# Instigator2012ControllerBoard.net
KiCad netlist of a schematic drawn in Altium Designer
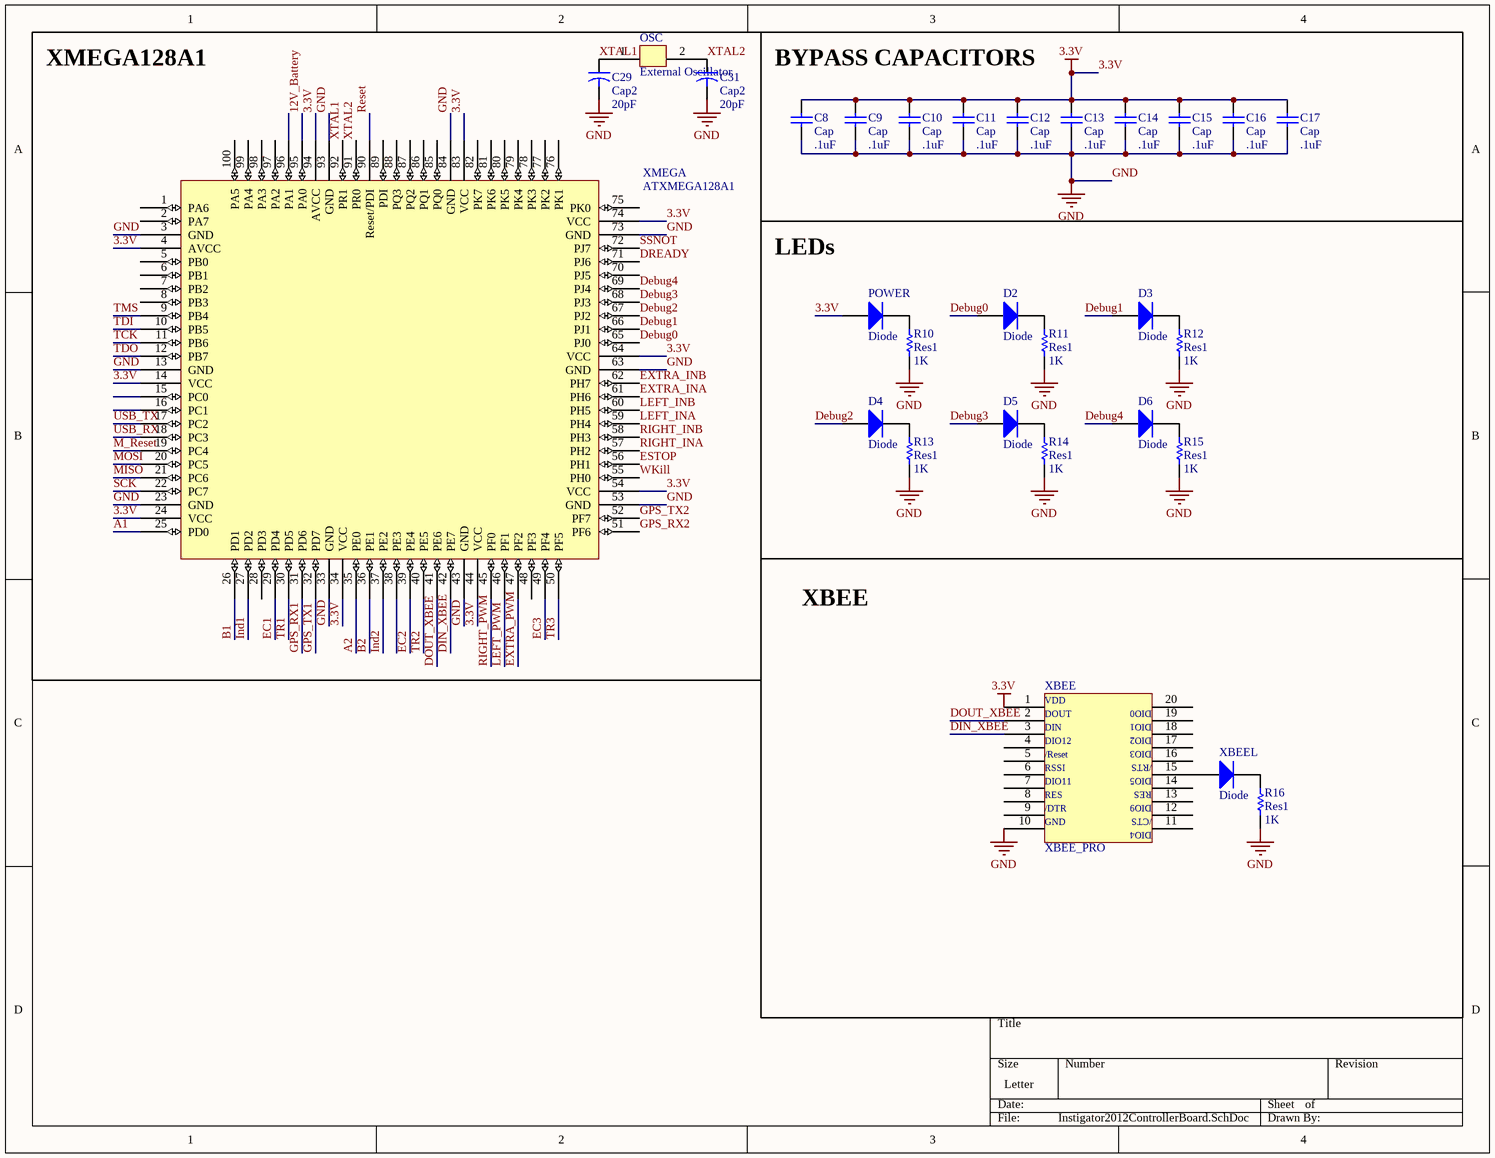
[diagram p0: Instigator2012ControllerBoard.SchDoc]

(export (version "E")
  (design (tool "Eeschema 10.0.6"))
  (components
    (comp (ref "C8")
      (value "Cap")
      (footprint "1608[0603]")
      (description "Capacitor")
      (fields (field (name "ALTIUM_VALUE") ".1uF") (field (name "PUBLISHER") "Altium Limited"))
      (libsource (lib "Miscellaneous Devices") (part "Cap"))
    )
    (comp (ref "C9")
      (value "Cap")
      (footprint "1608[0603]")
      (description "Capacitor")
      (fields (field (name "ALTIUM_VALUE") ".1uF") (field (name "PUBLISHER") "Altium Limited"))
      (libsource (lib "Miscellaneous Devices") (part "Cap"))
    )
    (comp (ref "C10")
      (value "Cap")
      (footprint "1608[0603]")
      (description "Capacitor")
      (fields (field (name "ALTIUM_VALUE") ".1uF") (field (name "PUBLISHER") "Altium Limited"))
      (libsource (lib "Miscellaneous Devices") (part "Cap"))
    )
    (comp (ref "C11")
      (value "Cap")
      (footprint "1608[0603]")
      (description "Capacitor")
      (fields (field (name "ALTIUM_VALUE") ".1uF") (field (name "PUBLISHER") "Altium Limited"))
      (libsource (lib "Miscellaneous Devices") (part "Cap"))
    )
    (comp (ref "C12")
      (value "Cap")
      (footprint "1608[0603]")
      (description "Capacitor")
      (fields (field (name "ALTIUM_VALUE") ".1uF") (field (name "PUBLISHER") "Altium Limited"))
      (libsource (lib "Miscellaneous Devices") (part "Cap"))
    )
    (comp (ref "C13")
      (value "Cap")
      (footprint "1608[0603]")
      (description "Capacitor")
      (fields (field (name "ALTIUM_VALUE") ".1uF") (field (name "PUBLISHER") "Altium Limited"))
      (libsource (lib "Miscellaneous Devices") (part "Cap"))
    )
    (comp (ref "C14")
      (value "Cap")
      (footprint "1608[0603]")
      (description "Capacitor")
      (fields (field (name "ALTIUM_VALUE") ".1uF") (field (name "PUBLISHER") "Altium Limited"))
      (libsource (lib "Miscellaneous Devices") (part "Cap"))
    )
    (comp (ref "C15")
      (value "Cap")
      (footprint "1608[0603]")
      (description "Capacitor")
      (fields (field (name "ALTIUM_VALUE") ".1uF") (field (name "PUBLISHER") "Altium Limited"))
      (libsource (lib "Miscellaneous Devices") (part "Cap"))
    )
    (comp (ref "C16")
      (value "Cap")
      (footprint "1608[0603]")
      (description "Capacitor")
      (fields (field (name "ALTIUM_VALUE") ".1uF") (field (name "PUBLISHER") "Altium Limited"))
      (libsource (lib "Miscellaneous Devices") (part "Cap"))
    )
    (comp (ref "C17")
      (value "Cap")
      (footprint "1608[0603]")
      (description "Capacitor")
      (fields (field (name "ALTIUM_VALUE") ".1uF") (field (name "PUBLISHER") "Altium Limited"))
      (libsource (lib "Miscellaneous Devices") (part "Cap"))
    )
    (comp (ref "C29")
      (value "Cap2")
      (footprint "1608[0603]")
      (description "Capacitor")
      (fields (field (name "ALTIUM_VALUE") "20pF") (field (name "PUBLISHER") "Altium Limited"))
      (libsource (lib "Miscellaneous Devices") (part "Cap2"))
    )
    (comp (ref "C31")
      (value "Cap2")
      (footprint "1608[0603]")
      (description "Capacitor")
      (fields (field (name "ALTIUM_VALUE") "20pF") (field (name "PUBLISHER") "Altium Limited"))
      (libsource (lib "Miscellaneous Devices") (part "Cap2"))
    )
    (comp (ref "D2")
      (value "Diode")
      (footprint "1608[0603]")
      (description "Default Diode")
      (fields (field (name "PUBLISHER") "Altium Limited"))
      (libsource (lib "Miscellaneous Devices") (part "Diode"))
    )
    (comp (ref "D3")
      (value "Diode")
      (footprint "1608[0603]")
      (description "Default Diode")
      (fields (field (name "PUBLISHER") "Altium Limited"))
      (libsource (lib "Miscellaneous Devices") (part "Diode"))
    )
    (comp (ref "D4")
      (value "Diode")
      (footprint "1608[0603]")
      (description "Default Diode")
      (fields (field (name "PUBLISHER") "Altium Limited"))
      (libsource (lib "Miscellaneous Devices") (part "Diode"))
    )
    (comp (ref "D5")
      (value "Diode")
      (footprint "1608[0603]")
      (description "Default Diode")
      (fields (field (name "PUBLISHER") "Altium Limited"))
      (libsource (lib "Miscellaneous Devices") (part "Diode"))
    )
    (comp (ref "D6")
      (value "Diode")
      (footprint "1608[0603]")
      (description "Default Diode")
      (fields (field (name "PUBLISHER") "Altium Limited"))
      (libsource (lib "Miscellaneous Devices") (part "Diode"))
    )
    (comp (ref "OSC")
      (value "External Oscillator")
      (footprint "PCBComponent_1 - duplicate3")
      (libsource (lib "VPOL5A_PowerRegulator") (part "External Oscillator"))
    )
    (comp (ref "POWER")
      (value "Diode")
      (footprint "1608[0603]")
      (description "Default Diode")
      (fields (field (name "PUBLISHER") "Altium Limited"))
      (libsource (lib "Miscellaneous Devices") (part "Diode"))
    )
    (comp (ref "R10")
      (value "Res1")
      (footprint "1608[0603]")
      (description "Resistor")
      (fields (field (name "ALTIUM_VALUE") "1K") (field (name "PUBLISHER") "Altium Limited"))
      (libsource (lib "Miscellaneous Devices") (part "Res1"))
    )
    (comp (ref "R11")
      (value "Res1")
      (footprint "1608[0603]")
      (description "Resistor")
      (fields (field (name "ALTIUM_VALUE") "1K") (field (name "PUBLISHER") "Altium Limited"))
      (libsource (lib "Miscellaneous Devices") (part "Res1"))
    )
    (comp (ref "R12")
      (value "Res1")
      (footprint "1608[0603]")
      (description "Resistor")
      (fields (field (name "ALTIUM_VALUE") "1K") (field (name "PUBLISHER") "Altium Limited"))
      (libsource (lib "Miscellaneous Devices") (part "Res1"))
    )
    (comp (ref "R13")
      (value "Res1")
      (footprint "1608[0603]")
      (description "Resistor")
      (fields (field (name "ALTIUM_VALUE") "1K") (field (name "PUBLISHER") "Altium Limited"))
      (libsource (lib "Miscellaneous Devices") (part "Res1"))
    )
    (comp (ref "R14")
      (value "Res1")
      (footprint "1608[0603]")
      (description "Resistor")
      (fields (field (name "ALTIUM_VALUE") "1K") (field (name "PUBLISHER") "Altium Limited"))
      (libsource (lib "Miscellaneous Devices") (part "Res1"))
    )
    (comp (ref "R15")
      (value "Res1")
      (footprint "1608[0603]")
      (description "Resistor")
      (fields (field (name "ALTIUM_VALUE") "1K") (field (name "PUBLISHER") "Altium Limited"))
      (libsource (lib "Miscellaneous Devices") (part "Res1"))
    )
    (comp (ref "R16")
      (value "Res1")
      (footprint "1608[0603]")
      (description "Resistor")
      (fields (field (name "ALTIUM_VALUE") "1K") (field (name "PUBLISHER") "Altium Limited"))
      (libsource (lib "Miscellaneous Devices") (part "Res1"))
    )
    (comp (ref "XBEE")
      (value "XBEE_PRO")
      (footprint "PCBComponent_1")
      (libsource (lib "XBEE_SOCKET") (part "XBEE"))
    )
    (comp (ref "XBEEL")
      (value "Diode")
      (footprint "1608[0603]")
      (description "Default Diode")
      (fields (field (name "PUBLISHER") "Altium Limited"))
      (libsource (lib "Miscellaneous Devices") (part "Diode"))
    )
    (comp (ref "XMEGA")
      (value "ATXMEGA128A1")
      (footprint "TSQFP50P1600X1600X120-100N")
      (libsource (lib "ATXMEGA128A1") (part "ATXMEGA128A1"))
    )
  )
  (nets
    (net (code "1") (name "/12V_Battery") (class "Default")
      (node (ref "XMEGA") (pin "95") (pinfunction "PA0_95") (pintype "bidirectional"))
    )
    (net (code "2") (name "/A1") (class "Default")
      (node (ref "XMEGA") (pin "25") (pinfunction "PD0_25") (pintype "bidirectional"))
    )
    (net (code "3") (name "/A2") (class "Default")
      (node (ref "XMEGA") (pin "35") (pinfunction "PE0_35") (pintype "bidirectional"))
    )
    (net (code "4") (name "/B1") (class "Default")
      (node (ref "XMEGA") (pin "26") (pinfunction "PD1_26") (pintype "bidirectional"))
    )
    (net (code "5") (name "/B2") (class "Default")
      (node (ref "XMEGA") (pin "36") (pinfunction "PE1_36") (pintype "bidirectional"))
    )
    (net (code "6") (name "/DIN_XBEE") (class "Default")
      (node (ref "XBEE") (pin "3") (pinfunction "3_3") (pintype "passive"))
      (node (ref "XMEGA") (pin "42") (pinfunction "PE7_42") (pintype "bidirectional"))
    )
    (net (code "7") (name "/DOUT_XBEE") (class "Default")
      (node (ref "XBEE") (pin "2") (pinfunction "2_2") (pintype "passive"))
      (node (ref "XMEGA") (pin "41") (pinfunction "PE6_41") (pintype "bidirectional"))
    )
    (net (code "8") (name "/DREADY") (class "Default")
      (node (ref "XMEGA") (pin "71") (pinfunction "PJ6_71") (pintype "bidirectional"))
    )
    (net (code "9") (name "/Debug0") (class "Default")
      (node (ref "D2") (pin "1") (pinfunction "A_1") (pintype "passive"))
      (node (ref "XMEGA") (pin "65") (pinfunction "PJ0_65") (pintype "bidirectional"))
    )
    (net (code "10") (name "/Debug1") (class "Default")
      (node (ref "D3") (pin "1") (pinfunction "A_1") (pintype "passive"))
      (node (ref "XMEGA") (pin "66") (pinfunction "PJ1_66") (pintype "bidirectional"))
    )
    (net (code "11") (name "/Debug2") (class "Default")
      (node (ref "D4") (pin "1") (pinfunction "A_1") (pintype "passive"))
      (node (ref "XMEGA") (pin "67") (pinfunction "PJ2_67") (pintype "bidirectional"))
    )
    (net (code "12") (name "/Debug3") (class "Default")
      (node (ref "D5") (pin "1") (pinfunction "A_1") (pintype "passive"))
      (node (ref "XMEGA") (pin "68") (pinfunction "PJ3_68") (pintype "bidirectional"))
    )
    (net (code "13") (name "/Debug4") (class "Default")
      (node (ref "D6") (pin "1") (pinfunction "A_1") (pintype "passive"))
      (node (ref "XMEGA") (pin "69") (pinfunction "PJ4_69") (pintype "bidirectional"))
    )
    (net (code "14") (name "/EC1") (class "Default")
      (node (ref "XMEGA") (pin "29") (pinfunction "PD4_29") (pintype "bidirectional"))
    )
    (net (code "15") (name "/EC2") (class "Default")
      (node (ref "XMEGA") (pin "39") (pinfunction "PE4_39") (pintype "bidirectional"))
    )
    (net (code "16") (name "/EC3") (class "Default")
      (node (ref "XMEGA") (pin "49") (pinfunction "PF4_49") (pintype "bidirectional"))
    )
    (net (code "17") (name "/ESTOP") (class "Default")
      (node (ref "XMEGA") (pin "56") (pinfunction "PH1_56") (pintype "bidirectional"))
    )
    (net (code "18") (name "/EXTRA_INA") (class "Default")
      (node (ref "XMEGA") (pin "61") (pinfunction "PH6_61") (pintype "bidirectional"))
    )
    (net (code "19") (name "/EXTRA_INB") (class "Default")
      (node (ref "XMEGA") (pin "62") (pinfunction "PH7_62") (pintype "bidirectional"))
    )
    (net (code "20") (name "/EXTRA_PWM") (class "Default")
      (node (ref "XMEGA") (pin "47") (pinfunction "PF2_47") (pintype "bidirectional"))
    )
    (net (code "21") (name "/GPS_RX1") (class "Default")
      (node (ref "XMEGA") (pin "31") (pinfunction "PD6_31") (pintype "bidirectional"))
    )
    (net (code "22") (name "/GPS_RX2") (class "Default")
      (node (ref "XMEGA") (pin "51") (pinfunction "PF6_51") (pintype "bidirectional"))
    )
    (net (code "23") (name "/GPS_TX1") (class "Default")
      (node (ref "XMEGA") (pin "32") (pinfunction "PD7_32") (pintype "bidirectional"))
    )
    (net (code "24") (name "/GPS_TX2") (class "Default")
      (node (ref "XMEGA") (pin "52") (pinfunction "PF7_52") (pintype "bidirectional"))
    )
    (net (code "25") (name "/Ind1") (class "Default")
      (node (ref "XMEGA") (pin "27") (pinfunction "PD2_27") (pintype "bidirectional"))
    )
    (net (code "26") (name "/Ind2") (class "Default")
      (node (ref "XMEGA") (pin "37") (pinfunction "PE2_37") (pintype "bidirectional"))
    )
    (net (code "27") (name "/LEFT_INA") (class "Default")
      (node (ref "XMEGA") (pin "59") (pinfunction "PH4_59") (pintype "bidirectional"))
    )
    (net (code "28") (name "/LEFT_INB") (class "Default")
      (node (ref "XMEGA") (pin "60") (pinfunction "PH5_60") (pintype "bidirectional"))
    )
    (net (code "29") (name "/LEFT_PWM") (class "Default")
      (node (ref "XMEGA") (pin "46") (pinfunction "PF1_46") (pintype "bidirectional"))
    )
    (net (code "30") (name "/MISO") (class "Default")
      (node (ref "XMEGA") (pin "21") (pinfunction "PC6_21") (pintype "bidirectional"))
    )
    (net (code "31") (name "/MOSI") (class "Default")
      (node (ref "XMEGA") (pin "20") (pinfunction "PC5_20") (pintype "bidirectional"))
    )
    (net (code "32") (name "/M_Reset") (class "Default")
      (node (ref "XMEGA") (pin "19") (pinfunction "PC4_19") (pintype "bidirectional"))
    )
    (net (code "33") (name "/RIGHT_INA") (class "Default")
      (node (ref "XMEGA") (pin "57") (pinfunction "PH2_57") (pintype "bidirectional"))
    )
    (net (code "34") (name "/RIGHT_INB") (class "Default")
      (node (ref "XMEGA") (pin "58") (pinfunction "PH3_58") (pintype "bidirectional"))
    )
    (net (code "35") (name "/RIGHT_PWM") (class "Default")
      (node (ref "XMEGA") (pin "45") (pinfunction "PF0_45") (pintype "bidirectional"))
    )
    (net (code "36") (name "/Reset") (class "Default")
      (node (ref "XMEGA") (pin "90") (pinfunction "Reset/PDI_90") (pintype "passive"))
    )
    (net (code "37") (name "/SCK") (class "Default")
      (node (ref "XMEGA") (pin "22") (pinfunction "PC7_22") (pintype "bidirectional"))
    )
    (net (code "38") (name "/SSNOT") (class "Default")
      (node (ref "XMEGA") (pin "72") (pinfunction "PJ7_72") (pintype "bidirectional"))
    )
    (net (code "39") (name "/TCK") (class "Default")
      (node (ref "XMEGA") (pin "11") (pinfunction "PB6_11") (pintype "bidirectional"))
    )
    (net (code "40") (name "/TDI") (class "Default")
      (node (ref "XMEGA") (pin "10") (pinfunction "PB5_10") (pintype "bidirectional"))
    )
    (net (code "41") (name "/TDO") (class "Default")
      (node (ref "XMEGA") (pin "12") (pinfunction "PB7_12") (pintype "bidirectional"))
    )
    (net (code "42") (name "/TMS") (class "Default")
      (node (ref "XMEGA") (pin "9") (pinfunction "PB4_9") (pintype "bidirectional"))
    )
    (net (code "43") (name "/TR1") (class "Default")
      (node (ref "XMEGA") (pin "30") (pinfunction "PD5_30") (pintype "bidirectional"))
    )
    (net (code "44") (name "/TR2") (class "Default")
      (node (ref "XMEGA") (pin "40") (pinfunction "PE5_40") (pintype "bidirectional"))
    )
    (net (code "45") (name "/TR3") (class "Default")
      (node (ref "XMEGA") (pin "50") (pinfunction "PF5_50") (pintype "bidirectional"))
    )
    (net (code "46") (name "/USB_RX") (class "Default")
      (node (ref "XMEGA") (pin "18") (pinfunction "PC3_18") (pintype "bidirectional"))
    )
    (net (code "47") (name "/USB_TX") (class "Default")
      (node (ref "XMEGA") (pin "17") (pinfunction "PC2_17") (pintype "bidirectional"))
    )
    (net (code "48") (name "/WKill") (class "Default")
      (node (ref "XMEGA") (pin "55") (pinfunction "PH0_55") (pintype "bidirectional"))
    )
    (net (code "49") (name "/XTAL1") (class "Default")
      (node (ref "C29") (pin "1") (pinfunction "1_1") (pintype "passive"))
      (node (ref "OSC") (pin "1") (pinfunction "1_1") (pintype "passive"))
      (node (ref "XMEGA") (pin "92") (pinfunction "PR1_92") (pintype "bidirectional"))
    )
    (net (code "50") (name "/XTAL2") (class "Default")
      (node (ref "C31") (pin "1") (pinfunction "1_1") (pintype "passive"))
      (node (ref "OSC") (pin "2") (pinfunction "2_2") (pintype "passive"))
      (node (ref "XMEGA") (pin "91") (pinfunction "PR0_91") (pintype "bidirectional"))
    )
    (net (code "51") (name "3.3V") (class "Default")
      (node (ref "C10") (pin "2") (pinfunction "2_2") (pintype "passive"))
      (node (ref "C11") (pin "2") (pinfunction "2_2") (pintype "passive"))
      (node (ref "C12") (pin "2") (pinfunction "2_2") (pintype "passive"))
      (node (ref "C13") (pin "2") (pinfunction "2_2") (pintype "passive"))
      (node (ref "C14") (pin "2") (pinfunction "2_2") (pintype "passive"))
      (node (ref "C15") (pin "2") (pinfunction "2_2") (pintype "passive"))
      (node (ref "C16") (pin "2") (pinfunction "2_2") (pintype "passive"))
      (node (ref "C17") (pin "2") (pinfunction "2_2") (pintype "passive"))
      (node (ref "C8") (pin "2") (pinfunction "2_2") (pintype "passive"))
      (node (ref "C9") (pin "2") (pinfunction "2_2") (pintype "passive"))
      (node (ref "POWER") (pin "1") (pinfunction "A_1") (pintype "passive"))
      (node (ref "XBEE") (pin "1") (pinfunction "1_1") (pintype "passive"))
      (node (ref "XMEGA") (pin "14") (pinfunction "VCC_14") (pintype "power_in"))
      (node (ref "XMEGA") (pin "24") (pinfunction "VCC_24") (pintype "power_in"))
      (node (ref "XMEGA") (pin "34") (pinfunction "VCC_34") (pintype "power_in"))
      (node (ref "XMEGA") (pin "4") (pinfunction "AVCC_4") (pintype "power_in"))
      (node (ref "XMEGA") (pin "44") (pinfunction "VCC_44") (pintype "power_in"))
      (node (ref "XMEGA") (pin "54") (pinfunction "VCC_54") (pintype "power_in"))
      (node (ref "XMEGA") (pin "64") (pinfunction "VCC_64") (pintype "power_in"))
      (node (ref "XMEGA") (pin "74") (pinfunction "VCC_74") (pintype "power_in"))
      (node (ref "XMEGA") (pin "83") (pinfunction "VCC_83") (pintype "power_in"))
      (node (ref "XMEGA") (pin "94") (pinfunction "AVCC_94") (pintype "power_in"))
    )
    (net (code "52") (name "GND") (class "Default")
      (node (ref "C10") (pin "1") (pinfunction "1_1") (pintype "passive"))
      (node (ref "C11") (pin "1") (pinfunction "1_1") (pintype "passive"))
      (node (ref "C12") (pin "1") (pinfunction "1_1") (pintype "passive"))
      (node (ref "C13") (pin "1") (pinfunction "1_1") (pintype "passive"))
      (node (ref "C14") (pin "1") (pinfunction "1_1") (pintype "passive"))
      (node (ref "C15") (pin "1") (pinfunction "1_1") (pintype "passive"))
      (node (ref "C16") (pin "1") (pinfunction "1_1") (pintype "passive"))
      (node (ref "C17") (pin "1") (pinfunction "1_1") (pintype "passive"))
      (node (ref "C29") (pin "2") (pinfunction "2_2") (pintype "passive"))
      (node (ref "C31") (pin "2") (pinfunction "2_2") (pintype "passive"))
      (node (ref "C8") (pin "1") (pinfunction "1_1") (pintype "passive"))
      (node (ref "C9") (pin "1") (pinfunction "1_1") (pintype "passive"))
      (node (ref "R10") (pin "1") (pinfunction "1_1") (pintype "passive"))
      (node (ref "R11") (pin "1") (pinfunction "1_1") (pintype "passive"))
      (node (ref "R12") (pin "1") (pinfunction "1_1") (pintype "passive"))
      (node (ref "R13") (pin "1") (pinfunction "1_1") (pintype "passive"))
      (node (ref "R14") (pin "1") (pinfunction "1_1") (pintype "passive"))
      (node (ref "R15") (pin "1") (pinfunction "1_1") (pintype "passive"))
      (node (ref "R16") (pin "1") (pinfunction "1_1") (pintype "passive"))
      (node (ref "XBEE") (pin "10") (pinfunction "10_10") (pintype "passive"))
      (node (ref "XMEGA") (pin "13") (pinfunction "GND_13") (pintype "power_in"))
      (node (ref "XMEGA") (pin "23") (pinfunction "GND_23") (pintype "power_in"))
      (node (ref "XMEGA") (pin "3") (pinfunction "GND_3") (pintype "power_in"))
      (node (ref "XMEGA") (pin "33") (pinfunction "GND_33") (pintype "power_in"))
      (node (ref "XMEGA") (pin "43") (pinfunction "GND_43") (pintype "power_in"))
      (node (ref "XMEGA") (pin "53") (pinfunction "GND_53") (pintype "power_in"))
      (node (ref "XMEGA") (pin "63") (pinfunction "GND_63") (pintype "power_in"))
      (node (ref "XMEGA") (pin "73") (pinfunction "GND_73") (pintype "power_in"))
      (node (ref "XMEGA") (pin "84") (pinfunction "GND_84") (pintype "power_in"))
      (node (ref "XMEGA") (pin "93") (pinfunction "GND_93") (pintype "power_in"))
    )
    (net (code "53") (name "Net-(D2-K)") (class "Default")
      (node (ref "D2") (pin "2") (pinfunction "K_2") (pintype "passive"))
      (node (ref "R11") (pin "2") (pinfunction "2_2") (pintype "passive"))
    )
    (net (code "54") (name "Net-(D3-K)") (class "Default")
      (node (ref "D3") (pin "2") (pinfunction "K_2") (pintype "passive"))
      (node (ref "R12") (pin "2") (pinfunction "2_2") (pintype "passive"))
    )
    (net (code "55") (name "Net-(D4-K)") (class "Default")
      (node (ref "D4") (pin "2") (pinfunction "K_2") (pintype "passive"))
      (node (ref "R13") (pin "2") (pinfunction "2_2") (pintype "passive"))
    )
    (net (code "56") (name "Net-(D5-K)") (class "Default")
      (node (ref "D5") (pin "2") (pinfunction "K_2") (pintype "passive"))
      (node (ref "R14") (pin "2") (pinfunction "2_2") (pintype "passive"))
    )
    (net (code "57") (name "Net-(D6-K)") (class "Default")
      (node (ref "D6") (pin "2") (pinfunction "K_2") (pintype "passive"))
      (node (ref "R15") (pin "2") (pinfunction "2_2") (pintype "passive"))
    )
    (net (code "58") (name "Net-(POWER-K)") (class "Default")
      (node (ref "POWER") (pin "2") (pinfunction "K_2") (pintype "passive"))
      (node (ref "R10") (pin "2") (pinfunction "2_2") (pintype "passive"))
    )
    (net (code "59") (name "Net-(XBEEL-A)") (class "Default")
      (node (ref "XBEE") (pin "15") (pinfunction "15_15") (pintype "passive"))
      (node (ref "XBEEL") (pin "1") (pinfunction "A_1") (pintype "passive"))
    )
    (net (code "60") (name "Net-(XBEEL-K)") (class "Default")
      (node (ref "R16") (pin "2") (pinfunction "2_2") (pintype "passive"))
      (node (ref "XBEEL") (pin "2") (pinfunction "K_2") (pintype "passive"))
    )
    (net (code "61") (name "unconnected-(XBEE-Pad4)") (class "Default")
      (node (ref "XBEE") (pin "4") (pinfunction "4_4") (pintype "passive"))
    )
    (net (code "62") (name "unconnected-(XBEE-Pad5)") (class "Default")
      (node (ref "XBEE") (pin "5") (pinfunction "5_5") (pintype "passive"))
    )
    (net (code "63") (name "unconnected-(XBEE-Pad6)") (class "Default")
      (node (ref "XBEE") (pin "6") (pinfunction "6_6") (pintype "passive"))
    )
    (net (code "64") (name "unconnected-(XBEE-Pad7)") (class "Default")
      (node (ref "XBEE") (pin "7") (pinfunction "7_7") (pintype "passive"))
    )
    (net (code "65") (name "unconnected-(XBEE-Pad8)") (class "Default")
      (node (ref "XBEE") (pin "8") (pinfunction "8_8") (pintype "passive"))
    )
    (net (code "66") (name "unconnected-(XBEE-Pad9)") (class "Default")
      (node (ref "XBEE") (pin "9") (pinfunction "9_9") (pintype "passive"))
    )
    (net (code "67") (name "unconnected-(XBEE-Pad11)") (class "Default")
      (node (ref "XBEE") (pin "11") (pinfunction "11_11") (pintype "passive"))
    )
    (net (code "68") (name "unconnected-(XBEE-Pad12)") (class "Default")
      (node (ref "XBEE") (pin "12") (pinfunction "12_12") (pintype "passive"))
    )
    (net (code "69") (name "unconnected-(XBEE-Pad13)") (class "Default")
      (node (ref "XBEE") (pin "13") (pinfunction "13_13") (pintype "passive"))
    )
    (net (code "70") (name "unconnected-(XBEE-Pad14)") (class "Default")
      (node (ref "XBEE") (pin "14") (pinfunction "14_14") (pintype "passive"))
    )
    (net (code "71") (name "unconnected-(XBEE-Pad16)") (class "Default")
      (node (ref "XBEE") (pin "16") (pinfunction "16_16") (pintype "passive"))
    )
    (net (code "72") (name "unconnected-(XBEE-Pad17)") (class "Default")
      (node (ref "XBEE") (pin "17") (pinfunction "17_17") (pintype "passive"))
    )
    (net (code "73") (name "unconnected-(XBEE-Pad18)") (class "Default")
      (node (ref "XBEE") (pin "18") (pinfunction "18_18") (pintype "passive"))
    )
    (net (code "74") (name "unconnected-(XBEE-Pad19)") (class "Default")
      (node (ref "XBEE") (pin "19") (pinfunction "19_19") (pintype "passive"))
    )
    (net (code "75") (name "unconnected-(XBEE-Pad20)") (class "Default")
      (node (ref "XBEE") (pin "20") (pinfunction "20_20") (pintype "passive"))
    )
    (net (code "76") (name "unconnected-(XMEGA-PA1-Pad96)") (class "Default")
      (node (ref "XMEGA") (pin "96") (pinfunction "PA1_96") (pintype "bidirectional"))
    )
    (net (code "77") (name "unconnected-(XMEGA-PA2-Pad97)") (class "Default")
      (node (ref "XMEGA") (pin "97") (pinfunction "PA2_97") (pintype "bidirectional"))
    )
    (net (code "78") (name "unconnected-(XMEGA-PA3-Pad98)") (class "Default")
      (node (ref "XMEGA") (pin "98") (pinfunction "PA3_98") (pintype "bidirectional"))
    )
    (net (code "79") (name "unconnected-(XMEGA-PA4-Pad99)") (class "Default")
      (node (ref "XMEGA") (pin "99") (pinfunction "PA4_99") (pintype "bidirectional"))
    )
    (net (code "80") (name "unconnected-(XMEGA-PA5-Pad100)") (class "Default")
      (node (ref "XMEGA") (pin "100") (pinfunction "PA5_100") (pintype "bidirectional"))
    )
    (net (code "81") (name "unconnected-(XMEGA-PA6-Pad1)") (class "Default")
      (node (ref "XMEGA") (pin "1") (pinfunction "PA6_1") (pintype "bidirectional"))
    )
    (net (code "82") (name "unconnected-(XMEGA-PA7-Pad2)") (class "Default")
      (node (ref "XMEGA") (pin "2") (pinfunction "PA7_2") (pintype "bidirectional"))
    )
    (net (code "83") (name "unconnected-(XMEGA-PB0-Pad5)") (class "Default")
      (node (ref "XMEGA") (pin "5") (pinfunction "PB0_5") (pintype "bidirectional"))
    )
    (net (code "84") (name "unconnected-(XMEGA-PB1-Pad6)") (class "Default")
      (node (ref "XMEGA") (pin "6") (pinfunction "PB1_6") (pintype "bidirectional"))
    )
    (net (code "85") (name "unconnected-(XMEGA-PB2-Pad7)") (class "Default")
      (node (ref "XMEGA") (pin "7") (pinfunction "PB2_7") (pintype "bidirectional"))
    )
    (net (code "86") (name "unconnected-(XMEGA-PB3-Pad8)") (class "Default")
      (node (ref "XMEGA") (pin "8") (pinfunction "PB3_8") (pintype "bidirectional"))
    )
    (net (code "87") (name "unconnected-(XMEGA-PC0-Pad15)") (class "Default")
      (node (ref "XMEGA") (pin "15") (pinfunction "PC0_15") (pintype "bidirectional"))
    )
    (net (code "88") (name "unconnected-(XMEGA-PC1-Pad16)") (class "Default")
      (node (ref "XMEGA") (pin "16") (pinfunction "PC1_16") (pintype "bidirectional"))
    )
    (net (code "89") (name "unconnected-(XMEGA-PD3-Pad28)") (class "Default")
      (node (ref "XMEGA") (pin "28") (pinfunction "PD3_28") (pintype "bidirectional"))
    )
    (net (code "90") (name "unconnected-(XMEGA-PDI-Pad89)") (class "Default")
      (node (ref "XMEGA") (pin "89") (pinfunction "PDI_89") (pintype "bidirectional"))
    )
    (net (code "91") (name "unconnected-(XMEGA-PE3-Pad38)") (class "Default")
      (node (ref "XMEGA") (pin "38") (pinfunction "PE3_38") (pintype "bidirectional"))
    )
    (net (code "92") (name "unconnected-(XMEGA-PF3-Pad48)") (class "Default")
      (node (ref "XMEGA") (pin "48") (pinfunction "PF3_48") (pintype "bidirectional"))
    )
    (net (code "93") (name "unconnected-(XMEGA-PJ5-Pad70)") (class "Default")
      (node (ref "XMEGA") (pin "70") (pinfunction "PJ5_70") (pintype "bidirectional"))
    )
    (net (code "94") (name "unconnected-(XMEGA-PK0-Pad75)") (class "Default")
      (node (ref "XMEGA") (pin "75") (pinfunction "PK0_75") (pintype "bidirectional"))
    )
    (net (code "95") (name "unconnected-(XMEGA-PK1-Pad76)") (class "Default")
      (node (ref "XMEGA") (pin "76") (pinfunction "PK1_76") (pintype "bidirectional"))
    )
    (net (code "96") (name "unconnected-(XMEGA-PK2-Pad77)") (class "Default")
      (node (ref "XMEGA") (pin "77") (pinfunction "PK2_77") (pintype "bidirectional"))
    )
    (net (code "97") (name "unconnected-(XMEGA-PK3-Pad78)") (class "Default")
      (node (ref "XMEGA") (pin "78") (pinfunction "PK3_78") (pintype "bidirectional"))
    )
    (net (code "98") (name "unconnected-(XMEGA-PK4-Pad79)") (class "Default")
      (node (ref "XMEGA") (pin "79") (pinfunction "PK4_79") (pintype "bidirectional"))
    )
    (net (code "99") (name "unconnected-(XMEGA-PK5-Pad80)") (class "Default")
      (node (ref "XMEGA") (pin "80") (pinfunction "PK5_80") (pintype "bidirectional"))
    )
    (net (code "100") (name "unconnected-(XMEGA-PK6-Pad81)") (class "Default")
      (node (ref "XMEGA") (pin "81") (pinfunction "PK6_81") (pintype "bidirectional"))
    )
    (net (code "101") (name "unconnected-(XMEGA-PK7-Pad82)") (class "Default")
      (node (ref "XMEGA") (pin "82") (pinfunction "PK7_82") (pintype "bidirectional"))
    )
    (net (code "102") (name "unconnected-(XMEGA-PQ0-Pad85)") (class "Default")
      (node (ref "XMEGA") (pin "85") (pinfunction "PQ0_85") (pintype "bidirectional"))
    )
    (net (code "103") (name "unconnected-(XMEGA-PQ1-Pad86)") (class "Default")
      (node (ref "XMEGA") (pin "86") (pinfunction "PQ1_86") (pintype "bidirectional"))
    )
    (net (code "104") (name "unconnected-(XMEGA-PQ2-Pad87)") (class "Default")
      (node (ref "XMEGA") (pin "87") (pinfunction "PQ2_87") (pintype "bidirectional"))
    )
    (net (code "105") (name "unconnected-(XMEGA-PQ3-Pad88)") (class "Default")
      (node (ref "XMEGA") (pin "88") (pinfunction "PQ3_88") (pintype "bidirectional"))
    )
  )
)
